# esp-prog.net
KiCad netlist of a schematic drawn in EAGLE
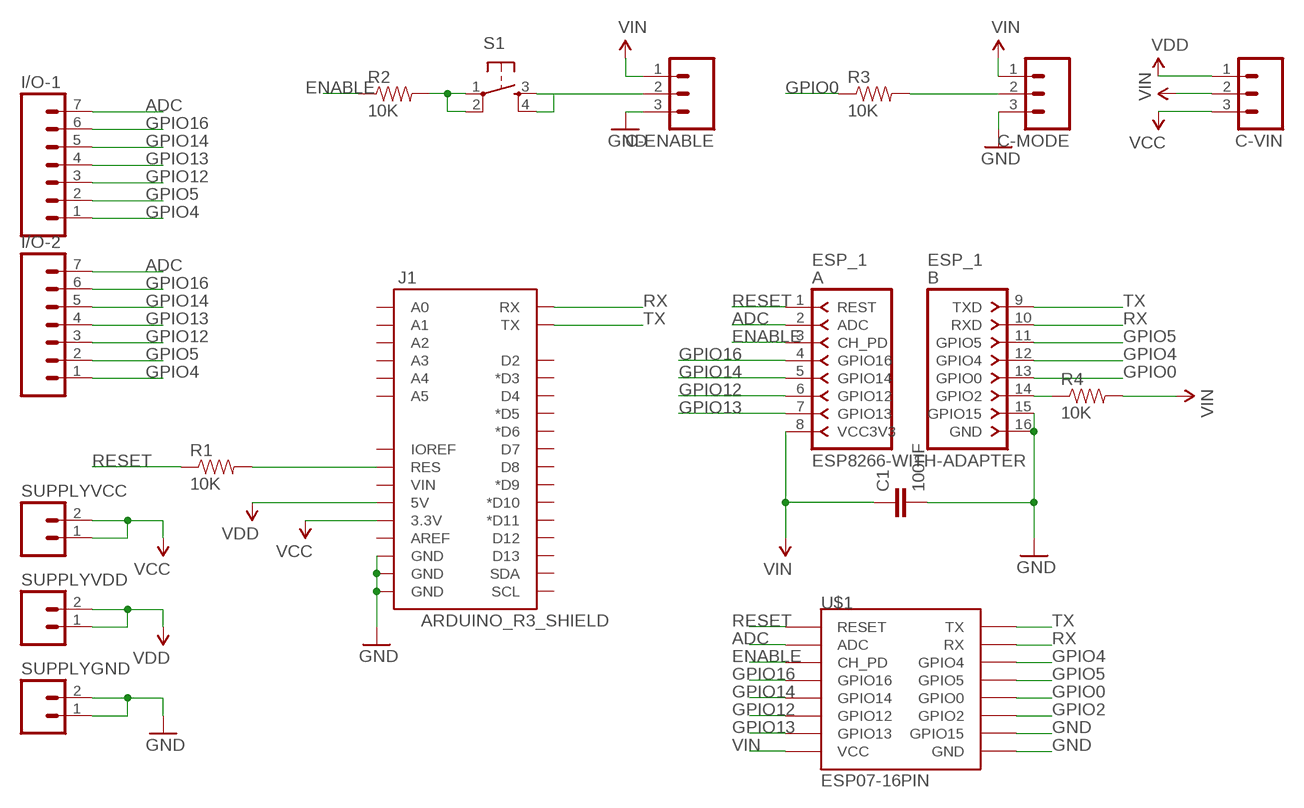
[diagram p0: schematic, sheet 1]

(export (version "E")
  (design (tool "Eeschema 10.0.6"))
  (components
    (comp (ref "C-ENABLE")
      (value "M031X03_NO_SILK")
      (footprint "eagle-import:1X03_NO_SILK")
      (libsource (lib "eagle-import") (part "M031X03_NO_SILK"))
    )
    (comp (ref "C-MODE")
      (value "M031X03_NO_SILK")
      (footprint "eagle-import:1X03_NO_SILK")
      (libsource (lib "eagle-import") (part "M031X03_NO_SILK"))
    )
    (comp (ref "C-VIN")
      (value "M031X03_NO_SILK")
      (footprint "eagle-import:1X03_NO_SILK")
      (libsource (lib "eagle-import") (part "M031X03_NO_SILK"))
    )
    (comp (ref "C1")
      (value "100nF")
      (footprint "eagle-import:0805")
      (libsource (lib "eagle-import") (part "CAP0805"))
    )
    (comp (ref "ESP_1")
      (value "ESP8266-WITH-ADAPTER")
      (footprint "eagle-import:ESP8266-ADAPTER")
      (libsource (lib "eagle-import") (part "ESP8266-WITH-ADAPTER"))
    )
    (comp (ref "I/O-1")
      (value "M07")
      (footprint "eagle-import:1X07")
      (libsource (lib "eagle-import") (part "M07"))
    )
    (comp (ref "I/O-2")
      (value "M07")
      (footprint "eagle-import:1X07")
      (libsource (lib "eagle-import") (part "M07"))
    )
    (comp (ref "J1")
      (value "ARDUINO_R3_SHIELD")
      (footprint "eagle-import:UNO_R3_SHIELD")
      (libsource (lib "eagle-import") (part "ARDUINO_R3_SHIELD"))
    )
    (comp (ref "R1")
      (value "10K")
      (footprint "eagle-import:0805")
      (libsource (lib "eagle-import") (part "RESISTOR0805-RES"))
    )
    (comp (ref "R2")
      (value "10K")
      (footprint "eagle-import:0805")
      (libsource (lib "eagle-import") (part "RESISTOR0805-RES"))
    )
    (comp (ref "R3")
      (value "10K")
      (footprint "eagle-import:0805")
      (libsource (lib "eagle-import") (part "RESISTOR0805-RES"))
    )
    (comp (ref "R4")
      (value "10K")
      (footprint "eagle-import:0805")
      (libsource (lib "eagle-import") (part "RESISTOR0805-RES"))
    )
    (comp (ref "S1")
      (value "TAC_SWITCHPTH")
      (footprint "eagle-import:TACTILE-PTH")
      (libsource (lib "eagle-import") (part "TAC_SWITCHPTH"))
    )
    (comp (ref "SUPPLYGND")
      (value "M02PTH")
      (footprint "eagle-import:1X02")
      (libsource (lib "eagle-import") (part "M02PTH"))
    )
    (comp (ref "SUPPLYVCC")
      (value "M02PTH")
      (footprint "eagle-import:1X02")
      (libsource (lib "eagle-import") (part "M02PTH"))
    )
    (comp (ref "SUPPLYVDD")
      (value "M02PTH")
      (footprint "eagle-import:1X02")
      (libsource (lib "eagle-import") (part "M02PTH"))
    )
    (comp (ref "U$1")
      (value "ESP07-16PIN")
      (footprint "eagle-import:ESP07-16PIN")
      (libsource (lib "eagle-import") (part "ESP07-16PIN"))
    )
  )
  (nets
    (net (code "1") (name "/ADC") (class "Default")
      (node (ref "ESP_1") (pin "2") (pinfunction "ADC_2") (pintype "passive"))
      (node (ref "I/O-1") (pin "7") (pinfunction "7_7") (pintype "passive"))
      (node (ref "I/O-2") (pin "7") (pinfunction "7_7") (pintype "passive"))
      (node (ref "U$1") (pin "ADC") (pinfunction "ADC_ADC") (pintype "bidirectional"))
    )
    (net (code "2") (name "/ENABLE") (class "Default")
      (node (ref "ESP_1") (pin "3") (pinfunction "CH_PD_3") (pintype "passive"))
      (node (ref "R2") (pin "1") (pinfunction "1_1") (pintype "passive"))
      (node (ref "U$1") (pin "CH_PD") (pinfunction "CH_PD_CH_PD") (pintype "bidirectional"))
    )
    (net (code "3") (name "/GPIO0") (class "Default")
      (node (ref "ESP_1") (pin "13") (pinfunction "GPIO0_13") (pintype "passive"))
      (node (ref "R3") (pin "1") (pinfunction "1_1") (pintype "passive"))
      (node (ref "U$1") (pin "GPIO0") (pinfunction "GPIO0_GPIO0") (pintype "bidirectional"))
    )
    (net (code "4") (name "/GPIO2") (class "Default")
      (node (ref "ESP_1") (pin "14") (pinfunction "GPIO2_14") (pintype "passive"))
      (node (ref "R4") (pin "1") (pinfunction "1_1") (pintype "passive"))
      (node (ref "U$1") (pin "GPIO2") (pinfunction "GPIO2_GPIO2") (pintype "bidirectional"))
    )
    (net (code "5") (name "/GPIO4") (class "Default")
      (node (ref "ESP_1") (pin "12") (pinfunction "GPIO4_12") (pintype "passive"))
      (node (ref "I/O-1") (pin "1") (pinfunction "1_1") (pintype "passive"))
      (node (ref "I/O-2") (pin "1") (pinfunction "1_1") (pintype "passive"))
      (node (ref "U$1") (pin "GPIO4") (pinfunction "GPIO4_GPIO4") (pintype "bidirectional"))
    )
    (net (code "6") (name "/GPIO5") (class "Default")
      (node (ref "ESP_1") (pin "11") (pinfunction "GPIO5_11") (pintype "passive"))
      (node (ref "I/O-1") (pin "2") (pinfunction "2_2") (pintype "passive"))
      (node (ref "I/O-2") (pin "2") (pinfunction "2_2") (pintype "passive"))
      (node (ref "U$1") (pin "GPIO5") (pinfunction "GPIO5_GPIO5") (pintype "bidirectional"))
    )
    (net (code "7") (name "/GPIO12") (class "Default")
      (node (ref "ESP_1") (pin "6") (pinfunction "GPIO12_6") (pintype "passive"))
      (node (ref "I/O-1") (pin "3") (pinfunction "3_3") (pintype "passive"))
      (node (ref "I/O-2") (pin "3") (pinfunction "3_3") (pintype "passive"))
      (node (ref "U$1") (pin "GPIO12") (pinfunction "GPIO12_GPIO12") (pintype "bidirectional"))
    )
    (net (code "8") (name "/GPIO13") (class "Default")
      (node (ref "ESP_1") (pin "7") (pinfunction "GPIO13_7") (pintype "passive"))
      (node (ref "I/O-1") (pin "4") (pinfunction "4_4") (pintype "passive"))
      (node (ref "I/O-2") (pin "4") (pinfunction "4_4") (pintype "passive"))
      (node (ref "U$1") (pin "GPIO13") (pinfunction "GPIO13_GPIO13") (pintype "bidirectional"))
    )
    (net (code "9") (name "/GPIO14") (class "Default")
      (node (ref "ESP_1") (pin "5") (pinfunction "GPIO14_5") (pintype "passive"))
      (node (ref "I/O-1") (pin "5") (pinfunction "5_5") (pintype "passive"))
      (node (ref "I/O-2") (pin "5") (pinfunction "5_5") (pintype "passive"))
      (node (ref "U$1") (pin "GPIO14") (pinfunction "GPIO14_GPIO14") (pintype "bidirectional"))
    )
    (net (code "10") (name "/GPIO16") (class "Default")
      (node (ref "ESP_1") (pin "4") (pinfunction "GPIO16_4") (pintype "passive"))
      (node (ref "I/O-1") (pin "6") (pinfunction "6_6") (pintype "passive"))
      (node (ref "I/O-2") (pin "6") (pinfunction "6_6") (pintype "passive"))
      (node (ref "U$1") (pin "GPIO16") (pinfunction "GPIO16_GPIO16") (pintype "bidirectional"))
    )
    (net (code "11") (name "/RESET") (class "Default")
      (node (ref "ESP_1") (pin "1") (pinfunction "REST_1") (pintype "passive"))
      (node (ref "R1") (pin "1") (pinfunction "1_1") (pintype "passive"))
      (node (ref "U$1") (pin "REST") (pinfunction "RESET_REST") (pintype "bidirectional"))
    )
    (net (code "12") (name "/RX") (class "Default")
      (node (ref "ESP_1") (pin "10") (pinfunction "RXD_10") (pintype "passive"))
      (node (ref "J1") (pin "RX") (pinfunction "RX_RX") (pintype "bidirectional"))
      (node (ref "U$1") (pin "RX") (pinfunction "RX_RX") (pintype "bidirectional"))
    )
    (net (code "13") (name "/TX") (class "Default")
      (node (ref "ESP_1") (pin "9") (pinfunction "TXD_9") (pintype "passive"))
      (node (ref "J1") (pin "TX") (pinfunction "TX_TX") (pintype "bidirectional"))
      (node (ref "U$1") (pin "TX") (pinfunction "TX_TX") (pintype "bidirectional"))
    )
    (net (code "14") (name "GND") (class "Default")
      (node (ref "C-ENABLE") (pin "3") (pinfunction "3_3") (pintype "passive"))
      (node (ref "C-MODE") (pin "3") (pinfunction "3_3") (pintype "passive"))
      (node (ref "C1") (pin "2") (pinfunction "2_2") (pintype "passive"))
      (node (ref "ESP_1") (pin "15") (pinfunction "GPIO15_15") (pintype "passive"))
      (node (ref "ESP_1") (pin "16") (pinfunction "GND_16") (pintype "passive"))
      (node (ref "J1") (pin "GND@0") (pinfunction "GND_GND@0") (pintype "bidirectional"))
      (node (ref "J1") (pin "GND@1") (pinfunction "GND_GND@1") (pintype "bidirectional"))
      (node (ref "J1") (pin "GND@2") (pinfunction "GND_GND@2") (pintype "bidirectional"))
      (node (ref "SUPPLYGND") (pin "1") (pinfunction "1_1") (pintype "passive"))
      (node (ref "SUPPLYGND") (pin "2") (pinfunction "2_2") (pintype "passive"))
      (node (ref "U$1") (pin "GND") (pinfunction "GND_GND") (pintype "bidirectional"))
      (node (ref "U$1") (pin "GPIO15") (pinfunction "GPIO15_GPIO15") (pintype "bidirectional"))
    )
    (net (code "15") (name "Net-(C-ENABLE-Pad2)") (class "Default")
      (node (ref "C-ENABLE") (pin "2") (pinfunction "2_2") (pintype "passive"))
      (node (ref "S1") (pin "3") (pinfunction "3_3") (pintype "passive"))
      (node (ref "S1") (pin "4") (pinfunction "4_4") (pintype "passive"))
    )
    (net (code "16") (name "Net-(C-MODE-Pad2)") (class "Default")
      (node (ref "C-MODE") (pin "2") (pinfunction "2_2") (pintype "passive"))
      (node (ref "R3") (pin "2") (pinfunction "2_2") (pintype "passive"))
    )
    (net (code "17") (name "Net-(J1-PadRES)") (class "Default")
      (node (ref "J1") (pin "RES") (pinfunction "RES_RES") (pintype "bidirectional"))
      (node (ref "R1") (pin "2") (pinfunction "2_2") (pintype "passive"))
    )
    (net (code "18") (name "Net-(R2-Pad2)") (class "Default")
      (node (ref "R2") (pin "2") (pinfunction "2_2") (pintype "passive"))
      (node (ref "S1") (pin "1") (pinfunction "1_1") (pintype "passive"))
      (node (ref "S1") (pin "2") (pinfunction "2_2") (pintype "passive"))
    )
    (net (code "19") (name "VCC") (class "Default")
      (node (ref "C-VIN") (pin "3") (pinfunction "3_3") (pintype "passive"))
      (node (ref "J1") (pin "3.3V") (pinfunction "3.3V_3.3V") (pintype "bidirectional"))
      (node (ref "SUPPLYVCC") (pin "1") (pinfunction "1_1") (pintype "passive"))
      (node (ref "SUPPLYVCC") (pin "2") (pinfunction "2_2") (pintype "passive"))
    )
    (net (code "20") (name "VDD") (class "Default")
      (node (ref "C-VIN") (pin "1") (pinfunction "1_1") (pintype "passive"))
      (node (ref "J1") (pin "5V") (pinfunction "5V_5V") (pintype "bidirectional"))
      (node (ref "SUPPLYVDD") (pin "1") (pinfunction "1_1") (pintype "passive"))
      (node (ref "SUPPLYVDD") (pin "2") (pinfunction "2_2") (pintype "passive"))
    )
    (net (code "21") (name "VIN") (class "Default")
      (node (ref "C-ENABLE") (pin "1") (pinfunction "1_1") (pintype "passive"))
      (node (ref "C-MODE") (pin "1") (pinfunction "1_1") (pintype "passive"))
      (node (ref "C-VIN") (pin "2") (pinfunction "2_2") (pintype "passive"))
      (node (ref "C1") (pin "1") (pinfunction "1_1") (pintype "passive"))
      (node (ref "ESP_1") (pin "8") (pinfunction "VCC3V3_8") (pintype "passive"))
      (node (ref "R4") (pin "2") (pinfunction "2_2") (pintype "passive"))
      (node (ref "U$1") (pin "VCC") (pinfunction "VCC_VCC") (pintype "bidirectional"))
    )
    (net (code "22") (name "unconnected-(J1-*D3-PadD3)") (class "Default")
      (node (ref "J1") (pin "D3") (pinfunction "*D3_D3") (pintype "bidirectional"))
    )
    (net (code "23") (name "unconnected-(J1-*D5-PadD5)") (class "Default")
      (node (ref "J1") (pin "D5") (pinfunction "*D5_D5") (pintype "bidirectional"))
    )
    (net (code "24") (name "unconnected-(J1-*D6-PadD6)") (class "Default")
      (node (ref "J1") (pin "D6") (pinfunction "*D6_D6") (pintype "bidirectional"))
    )
    (net (code "25") (name "unconnected-(J1-*D9-PadD9)") (class "Default")
      (node (ref "J1") (pin "D9") (pinfunction "*D9_D9") (pintype "bidirectional"))
    )
    (net (code "26") (name "unconnected-(J1-*D10-PadD10)") (class "Default")
      (node (ref "J1") (pin "D10") (pinfunction "*D10_D10") (pintype "bidirectional"))
    )
    (net (code "27") (name "unconnected-(J1-*D11-PadD11)") (class "Default")
      (node (ref "J1") (pin "D11") (pinfunction "*D11_D11") (pintype "bidirectional"))
    )
    (net (code "28") (name "unconnected-(J1-PadA0)") (class "Default")
      (node (ref "J1") (pin "A0") (pinfunction "A0_A0") (pintype "bidirectional"))
    )
    (net (code "29") (name "unconnected-(J1-PadA1)") (class "Default")
      (node (ref "J1") (pin "A1") (pinfunction "A1_A1") (pintype "bidirectional"))
    )
    (net (code "30") (name "unconnected-(J1-PadA2)") (class "Default")
      (node (ref "J1") (pin "A2") (pinfunction "A2_A2") (pintype "bidirectional"))
    )
    (net (code "31") (name "unconnected-(J1-PadA3)") (class "Default")
      (node (ref "J1") (pin "A3") (pinfunction "A3_A3") (pintype "bidirectional"))
    )
    (net (code "32") (name "unconnected-(J1-PadA4)") (class "Default")
      (node (ref "J1") (pin "A4") (pinfunction "A4_A4") (pintype "bidirectional"))
    )
    (net (code "33") (name "unconnected-(J1-PadA5)") (class "Default")
      (node (ref "J1") (pin "A5") (pinfunction "A5_A5") (pintype "bidirectional"))
    )
    (net (code "34") (name "unconnected-(J1-PadAREF)") (class "Default")
      (node (ref "J1") (pin "AREF") (pinfunction "AREF_AREF") (pintype "bidirectional"))
    )
    (net (code "35") (name "unconnected-(J1-PadD2)") (class "Default")
      (node (ref "J1") (pin "D2") (pinfunction "D2_D2") (pintype "bidirectional"))
    )
    (net (code "36") (name "unconnected-(J1-PadD4)") (class "Default")
      (node (ref "J1") (pin "D4") (pinfunction "D4_D4") (pintype "bidirectional"))
    )
    (net (code "37") (name "unconnected-(J1-PadD7)") (class "Default")
      (node (ref "J1") (pin "D7") (pinfunction "D7_D7") (pintype "bidirectional"))
    )
    (net (code "38") (name "unconnected-(J1-PadD8)") (class "Default")
      (node (ref "J1") (pin "D8") (pinfunction "D8_D8") (pintype "bidirectional"))
    )
    (net (code "39") (name "unconnected-(J1-PadD12)") (class "Default")
      (node (ref "J1") (pin "D12") (pinfunction "D12_D12") (pintype "bidirectional"))
    )
    (net (code "40") (name "unconnected-(J1-PadD13)") (class "Default")
      (node (ref "J1") (pin "D13") (pinfunction "D13_D13") (pintype "bidirectional"))
    )
    (net (code "41") (name "unconnected-(J1-PadIOREF)") (class "Default")
      (node (ref "J1") (pin "IOREF") (pinfunction "IOREF_IOREF") (pintype "bidirectional"))
    )
    (net (code "42") (name "unconnected-(J1-PadSCL)") (class "Default")
      (node (ref "J1") (pin "SCL") (pinfunction "SCL_SCL") (pintype "bidirectional"))
    )
    (net (code "43") (name "unconnected-(J1-PadSDA)") (class "Default")
      (node (ref "J1") (pin "SDA") (pinfunction "SDA_SDA") (pintype "bidirectional"))
    )
    (net (code "44") (name "unconnected-(J1-PadVIN)") (class "Default")
      (node (ref "J1") (pin "VIN") (pinfunction "VIN_VIN") (pintype "bidirectional"))
    )
  )
)
